# Power.net
KiCad netlist of a schematic drawn in Altium Designer
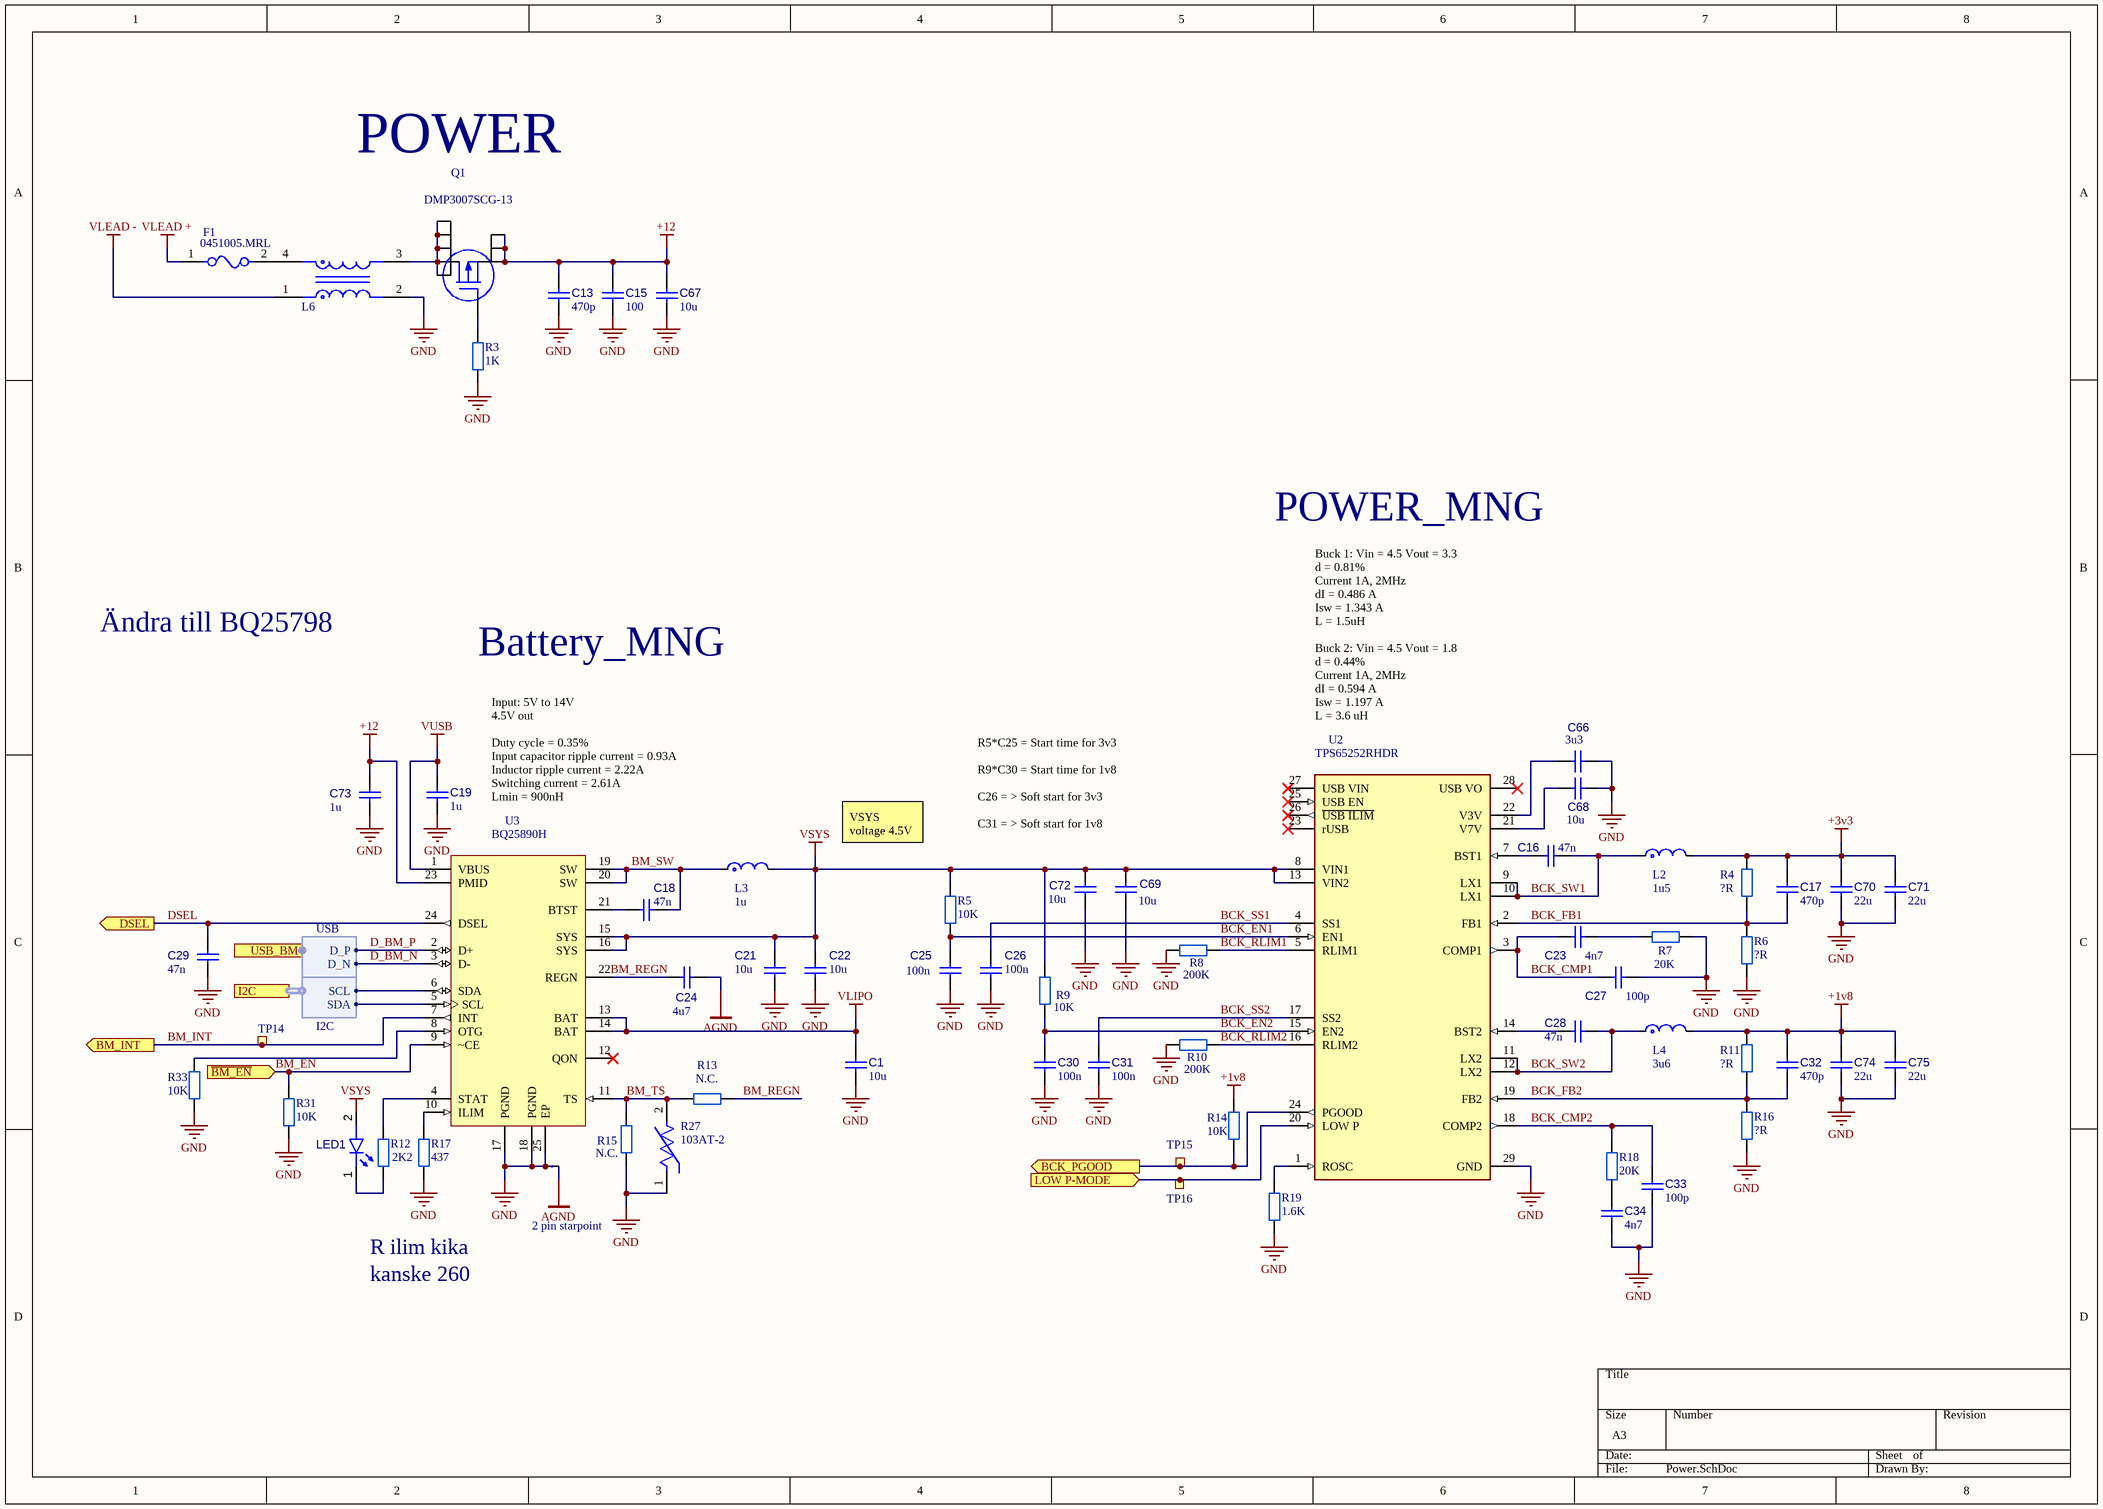
[diagram p0: Power.SchDoc]

(export (version "E")
  (design (tool "Eeschema 10.0.6"))
  (components
    (comp (ref "C1")
      (value "10u")
      (footprint "CAPC1608X90X40LL10T20 HD")
      (description "Chip Capacitor, 0603 (1608 Metric)")
      (fields (field (name "TOLERANCE") "?%") (field (name "Comment") "Capacitor 0603"))
      (libsource (lib "Motonaut") (part "CAP-NP-2"))
    )
    (comp (ref "C13")
      (value "470p")
      (footprint "CAPC2013X95X50LL10T25 HD")
      (description "Chip Capacitor, 0805 (2012 Metric)")
      (fields (field (name "TOLERANCE") "?%") (field (name "Comment") "Capacitor 0805"))
      (libsource (lib "Motonaut") (part "CAP-NP-2"))
    )
    (comp (ref "C15")
      (value "100")
      (footprint "CAPC1608X90X40LL10T20 HD")
      (description "Chip Capacitor, 0603 (1608 Metric)")
      (fields (field (name "TOLERANCE") "?%") (field (name "Comment") "Capacitor 0603"))
      (libsource (lib "Motonaut") (part "CAP-NP-2"))
    )
    (comp (ref "C16")
      (value "47n")
      (footprint "CAPC1005X55X25LL05T10 HD")
      (description "Chip Capacitor, 0402 (1005 Metric)")
      (fields (field (name "TOLERANCE") "?%") (field (name "Comment") "Capacitor 0402"))
      (libsource (lib "Motonaut") (part "CAP-NP-2"))
    )
    (comp (ref "C17")
      (value "470p")
      (footprint "CAPC1005X55X25LL05T10 HD")
      (description "Chip Capacitor, 0402 (1005 Metric)")
      (fields (field (name "TOLERANCE") "?%") (field (name "Comment") "Capacitor 0402"))
      (libsource (lib "Motonaut") (part "CAP-NP-2"))
    )
    (comp (ref "C18")
      (value "47n")
      (footprint "CAPC1005X55X25LL05T10 HD")
      (description "Chip Capacitor, 0402 (1005 Metric)")
      (fields (field (name "TOLERANCE") "?%") (field (name "Comment") "Capacitor 0402"))
      (libsource (lib "Motonaut") (part "CAP-NP-2"))
    )
    (comp (ref "C19")
      (value "1u")
      (footprint "CAPC1005X55X25LL05T10 HD")
      (description "Chip Capacitor, 0402 (1005 Metric)")
      (fields (field (name "TOLERANCE") "?%") (field (name "Comment") "Capacitor 0402"))
      (libsource (lib "Motonaut") (part "CAP-NP-2"))
    )
    (comp (ref "C21")
      (value "10u")
      (footprint "CAPC1608X90X40LL10T20 HD")
      (description "Chip Capacitor, 0603 (1608 Metric)")
      (fields (field (name "TOLERANCE") "?%") (field (name "Comment") "Capacitor 0603"))
      (libsource (lib "Motonaut") (part "CAP-NP-2"))
    )
    (comp (ref "C22")
      (value "10u")
      (footprint "CAPC1608X90X40LL10T20 HD")
      (description "Chip Capacitor, 0603 (1608 Metric)")
      (fields (field (name "TOLERANCE") "?%") (field (name "Comment") "Capacitor 0603"))
      (libsource (lib "Motonaut") (part "CAP-NP-2"))
    )
    (comp (ref "C23")
      (value "4n7")
      (footprint "CAPC1005X55X25LL05T10 HD")
      (description "Chip Capacitor, 0402 (1005 Metric)")
      (fields (field (name "TOLERANCE") "?%") (field (name "Comment") "Capacitor 0402"))
      (libsource (lib "Motonaut") (part "CAP-NP-2"))
    )
    (comp (ref "C24")
      (value "4u7")
      (footprint "CAPC1608X90X40LL10T20 HD")
      (description "Chip Capacitor, 0603 (1608 Metric)")
      (fields (field (name "TOLERANCE") "?%") (field (name "Comment") "Capacitor 0603"))
      (libsource (lib "Motonaut") (part "CAP-NP-2"))
    )
    (comp (ref "C25")
      (value "100n")
      (footprint "CAPC1005X55X25LL05T10 HD")
      (description "Chip Capacitor, 0402 (1005 Metric)")
      (fields (field (name "TOLERANCE") "?%") (field (name "Comment") "Capacitor 0402"))
      (libsource (lib "Motonaut") (part "CAP-NP-2"))
    )
    (comp (ref "C26")
      (value "100n")
      (footprint "CAPC1005X55X25LL05T10 HD")
      (description "Chip Capacitor, 0402 (1005 Metric)")
      (fields (field (name "TOLERANCE") "?%") (field (name "Comment") "Capacitor 0402"))
      (libsource (lib "Motonaut") (part "CAP-NP-2"))
    )
    (comp (ref "C27")
      (value "100p")
      (footprint "CAPC1005X55X25LL05T10 HD")
      (description "Chip Capacitor, 0402 (1005 Metric)")
      (fields (field (name "TOLERANCE") "?%") (field (name "Comment") "Capacitor 0402"))
      (libsource (lib "Motonaut") (part "CAP-NP-2"))
    )
    (comp (ref "C28")
      (value "47n")
      (footprint "CAPC1005X55X25LL05T10 HD")
      (description "Chip Capacitor, 0402 (1005 Metric)")
      (fields (field (name "TOLERANCE") "?%") (field (name "Comment") "Capacitor 0402"))
      (libsource (lib "Motonaut") (part "CAP-NP-2"))
    )
    (comp (ref "C29")
      (value "47n")
      (footprint "CAPC1005X55X25LL05T10 HD")
      (description "Chip Capacitor, 0402 (1005 Metric)")
      (fields (field (name "TOLERANCE") "?%") (field (name "Comment") "Capacitor 0402"))
      (libsource (lib "Motonaut") (part "CAP-NP-2"))
    )
    (comp (ref "C30")
      (value "100n")
      (footprint "CAPC1005X55X25LL05T10 HD")
      (description "Chip Capacitor, 0402 (1005 Metric)")
      (fields (field (name "TOLERANCE") "?%") (field (name "Comment") "Capacitor 0402"))
      (libsource (lib "Motonaut") (part "CAP-NP-2"))
    )
    (comp (ref "C31")
      (value "100n")
      (footprint "CAPC1005X55X25LL05T10 HD")
      (description "Chip Capacitor, 0402 (1005 Metric)")
      (fields (field (name "TOLERANCE") "?%") (field (name "Comment") "Capacitor 0402"))
      (libsource (lib "Motonaut") (part "CAP-NP-2"))
    )
    (comp (ref "C32")
      (value "470p")
      (footprint "CAPC1005X55X25LL05T10 HD")
      (description "Chip Capacitor, 0402 (1005 Metric)")
      (fields (field (name "TOLERANCE") "?%") (field (name "Comment") "Capacitor 0402"))
      (libsource (lib "Motonaut") (part "CAP-NP-2"))
    )
    (comp (ref "C33")
      (value "100p")
      (footprint "CAPC1005X55X25LL05T10 HD")
      (description "Chip Capacitor, 0402 (1005 Metric)")
      (fields (field (name "TOLERANCE") "?%") (field (name "Comment") "Capacitor 0402"))
      (libsource (lib "Motonaut") (part "CAP-NP-2"))
    )
    (comp (ref "C34")
      (value "4n7")
      (footprint "CAPC1005X55X25LL05T10 HD")
      (description "Chip Capacitor, 0402 (1005 Metric)")
      (fields (field (name "TOLERANCE") "?%") (field (name "Comment") "Capacitor 0402"))
      (libsource (lib "Motonaut") (part "CAP-NP-2"))
    )
    (comp (ref "C66")
      (value "3u3")
      (footprint "CAPC1608X90X40LL10T20 HD")
      (description "Chip Capacitor, 0603 (1608 Metric)")
      (fields (field (name "TOLERANCE") "?%") (field (name "Comment") "Capacitor 0603"))
      (libsource (lib "Motonaut") (part "CAP-NP-2"))
    )
    (comp (ref "C67")
      (value "10u")
      (footprint "CAPC1608X90X40LL10T20 HD")
      (description "Chip Capacitor, 0603 (1608 Metric)")
      (fields (field (name "TOLERANCE") "?%") (field (name "Comment") "Capacitor 0603"))
      (libsource (lib "Motonaut") (part "CAP-NP-2"))
    )
    (comp (ref "C68")
      (value "10u")
      (footprint "CAPC1608X90X40LL10T20 HD")
      (description "Chip Capacitor, 0603 (1608 Metric)")
      (fields (field (name "TOLERANCE") "?%") (field (name "Comment") "Capacitor 0603"))
      (libsource (lib "Motonaut") (part "CAP-NP-2"))
    )
    (comp (ref "C69")
      (value "10u")
      (footprint "CAPC1608X90X40LL10T20 HD")
      (description "Chip Capacitor, 0603 (1608 Metric)")
      (fields (field (name "TOLERANCE") "?%") (field (name "Comment") "Capacitor 0603"))
      (libsource (lib "Motonaut") (part "CAP-NP-2"))
    )
    (comp (ref "C70")
      (value "22u")
      (footprint "CAPC1608X90X40LL10T20 HD")
      (description "Chip Capacitor, 0603 (1608 Metric)")
      (fields (field (name "TOLERANCE") "?%") (field (name "Comment") "Capacitor 0603"))
      (libsource (lib "Motonaut") (part "CAP-NP-2"))
    )
    (comp (ref "C71")
      (value "22u")
      (footprint "CAPC1608X90X40LL10T20 HD")
      (description "Chip Capacitor, 0603 (1608 Metric)")
      (fields (field (name "TOLERANCE") "?%") (field (name "Comment") "Capacitor 0603"))
      (libsource (lib "Motonaut") (part "CAP-NP-2"))
    )
    (comp (ref "C72")
      (value "10u")
      (footprint "CAPC1608X90X40LL10T20 HD")
      (description "Chip Capacitor, 0603 (1608 Metric)")
      (fields (field (name "TOLERANCE") "?%") (field (name "Comment") "Capacitor 0603"))
      (libsource (lib "Motonaut") (part "CAP-NP-2"))
    )
    (comp (ref "C73")
      (value "1u")
      (footprint "CAPC1005X55X25LL05T10 HD")
      (description "Chip Capacitor, 0402 (1005 Metric)")
      (fields (field (name "TOLERANCE") "?%") (field (name "Comment") "Capacitor 0402"))
      (libsource (lib "Motonaut") (part "CAP-NP-2"))
    )
    (comp (ref "C74")
      (value "22u")
      (footprint "CAPC1608X90X40LL10T20 HD")
      (description "Chip Capacitor, 0603 (1608 Metric)")
      (fields (field (name "TOLERANCE") "?%") (field (name "Comment") "Capacitor 0603"))
      (libsource (lib "Motonaut") (part "CAP-NP-2"))
    )
    (comp (ref "C75")
      (value "22u")
      (footprint "CAPC1608X90X40LL10T20 HD")
      (description "Chip Capacitor, 0603 (1608 Metric)")
      (fields (field (name "TOLERANCE") "?%") (field (name "Comment") "Capacitor 0603"))
      (libsource (lib "Motonaut") (part "CAP-NP-2"))
    )
    (comp (ref "F1")
      (value "0451005.MRL")
      (footprint "FP-0451-MFG")
      (description "FUSE BRD MNT 5A 125VAC/VDC 2SMD")
      (fields
        (field (name "OCTOPART") "https://octopart.com/0451005.mrl-littelfuse-566389")
        (field (name "MANUFACTURER") "Littelfuse Inc")
      )
      (libsource (lib "Altium Content Vault") (part "5bcf9b9f640e542cf0359d10258e979"))
    )
    (comp (ref "L2")
      (value "1u5")
      (footprint "INDC2013X105X50NL20T20")
      (description "Inductor RF Chip Thin Film 0805")
      (fields (field (name "Comment") "Inductor 0805"))
      (libsource (lib "Motonaut") (part "4cc4b267dca4c8e51f7102f422741d8"))
    )
    (comp (ref "L3")
      (value "Inductor 0805")
      (footprint "INDC2013X105X50NL20T20")
      (description "Inductor RF Chip Thin Film 0805")
      (fields (field (name "INDUCTANCE") "1u"))
      (libsource (lib "Motonaut") (part "4cc4b267dca4c8e51f7102f422741d8"))
    )
    (comp (ref "L4")
      (value "3u6")
      (footprint "INDC2013X105X50NL20T20")
      (description "Inductor RF Chip Thin Film 0805")
      (fields (field (name "Comment") "Inductor 0805"))
      (libsource (lib "Motonaut") (part "4cc4b267dca4c8e51f7102f422741d8"))
    )
    (comp (ref "L6")
      (value "DLW5ATN231TQ2L")
      (footprint "FP-DLW5A-MFG")
      (description "Ind Common Mode Choke Wirewound 230 Ohm 100MHz 4A Embossed T/R")
      (libsource (lib "Motonaut") (part "7887baa02bf09715630a48d0c47d7b1"))
    )
    (comp (ref "LED1")
      (value "QBLP595-R")
      (footprint "QTB-QBLP595_V")
      (description "Chip LED 0402, Red, 0.02 A, 2.0 to 2.5 V, -40 to 80 degC, 2-Pin SMD, RoHS, Tape and Reel")
      (libsource (lib "Motonaut") (part "LED-KA-2"))
    )
    (comp (ref "Q1")
      (value "DMP3007SCG-13")
      (footprint "DMP3007SCG13")
      (description "Trans MOSFET P-CH 30V 50A 8-Pin VDFN EP T/R")
      (fields (field (name "MOUSER PART NUMBER") "621-DMP3007SCG-13"))
      (libsource (lib "Motonaut") (part "TRANS-MOSFET-3"))
    )
    (comp (ref "R3")
      (value "1K")
      (footprint "RESC1005X40X25LL10T10 HD")
      (description "Resistor 0403")
      (libsource (lib "Motonaut") (part "Resistor EU"))
    )
    (comp (ref "R4")
      (value "?R")
      (footprint "RESC1005X40X25LL10T10 HD")
      (description "Resistor 0403")
      (libsource (lib "Motonaut") (part "Resistor EU"))
    )
    (comp (ref "R5")
      (value "10K")
      (footprint "RESC1005X40X25LL10T10 HD")
      (description "Resistor 0403")
      (libsource (lib "Motonaut") (part "Resistor EU"))
    )
    (comp (ref "R6")
      (value "?R")
      (footprint "RESC1005X40X25LL10T10 HD")
      (description "Resistor 0403")
      (libsource (lib "Motonaut") (part "Resistor EU"))
    )
    (comp (ref "R7")
      (value "20K")
      (footprint "RESC1005X40X25LL10T10 HD")
      (description "Resistor 0403")
      (libsource (lib "Motonaut") (part "Resistor EU"))
    )
    (comp (ref "R8")
      (value "200K")
      (footprint "RESC1005X40X25LL10T10 HD")
      (description "Resistor 0403")
      (libsource (lib "Motonaut") (part "Resistor EU"))
    )
    (comp (ref "R9")
      (value "10K")
      (footprint "RESC1005X40X25LL10T10 HD")
      (description "Resistor 0403")
      (libsource (lib "Motonaut") (part "Resistor EU"))
    )
    (comp (ref "R10")
      (value "200K")
      (footprint "RESC1005X40X25LL10T10 HD")
      (description "Resistor 0403")
      (libsource (lib "Motonaut") (part "Resistor EU"))
    )
    (comp (ref "R11")
      (value "?R")
      (footprint "RESC1005X40X25LL10T10 HD")
      (description "Resistor 0403")
      (libsource (lib "Motonaut") (part "Resistor EU"))
    )
    (comp (ref "R12")
      (value "2K2")
      (footprint "RESC1005X40X25LL10T10 HD")
      (description "Resistor 0403")
      (libsource (lib "Motonaut") (part "Resistor EU"))
    )
    (comp (ref "R13")
      (value "N.C.")
      (footprint "RESC1005X40X25LL10T10 HD")
      (description "Resistor 0403")
      (libsource (lib "Motonaut") (part "Resistor EU"))
    )
    (comp (ref "R14")
      (value "10K")
      (footprint "RESC1005X40X25LL10T10 HD")
      (description "Resistor 0403")
      (libsource (lib "Motonaut") (part "Resistor EU"))
    )
    (comp (ref "R15")
      (value "N.C.")
      (footprint "RESC1005X40X25LL10T10 HD")
      (description "Resistor 0403")
      (libsource (lib "Motonaut") (part "Resistor EU"))
    )
    (comp (ref "R16")
      (value "?R")
      (footprint "RESC1005X40X25LL10T10 HD")
      (description "Resistor 0403")
      (libsource (lib "Motonaut") (part "Resistor EU"))
    )
    (comp (ref "R17")
      (value "437")
      (footprint "RESC1005X40X25LL10T10 HD")
      (description "Resistor 0403")
      (libsource (lib "Motonaut") (part "Resistor EU"))
    )
    (comp (ref "R18")
      (value "20K")
      (footprint "RESC1005X40X25LL10T10 HD")
      (description "Resistor 0403")
      (libsource (lib "Motonaut") (part "Resistor EU"))
    )
    (comp (ref "R19")
      (value "1.6K")
      (footprint "RESC1005X40X25LL10T10 HD")
      (description "Resistor 0403")
      (libsource (lib "Motonaut") (part "Resistor EU"))
    )
    (comp (ref "R27")
      (value "103AT-2")
      (footprint "FP-103AT-2-MFG")
      (description "Thermistor NTC 10KOhm 1% 2-Pin")
      (fields (field (name "TOLERANCE") "1%"))
      (libsource (lib "Altium Content Vault") (part "3b148a6ebabc5fb4d708a66c052d352"))
    )
    (comp (ref "R31")
      (value "10K")
      (footprint "RESC1005X40X25LL10T10 HD")
      (description "Resistor 0403")
      (libsource (lib "Motonaut") (part "Resistor EU"))
    )
    (comp (ref "R33")
      (value "10K")
      (footprint "RESC1005X40X25LL10T10 HD")
      (description "Resistor 0403")
      (libsource (lib "Motonaut") (part "Resistor EU"))
    )
    (comp (ref "ST1")
      (value "2 pin starpoint")
      (footprint "2 PIN STARPOINT")
      (description "Starpoint")
      (fields (field (name "MANUFACTURER PART NUMBER") "N.A."))
      (libsource (lib "Motonaut") (part "2 pin starpoint"))
    )
    (comp (ref "TP14")
      (value "TP_SMD_Ø0.7MM")
      (footprint "TP_SMD_Ø0.7mm")
      (description "0.7mm circular SMD testpad")
      (fields
        (field (name "MANUFACTURER") "Nordic Semiconductor")
        (field (name "MANUFACTURER PART NUMBER") "N.A.")
      )
      (libsource (lib "") (part "TP_SMD_Ø1.5MM_1"))
    )
    (comp (ref "TP15")
      (value "TP_SMD_Ø0.7MM")
      (footprint "TP_SMD_Ø0.7mm")
      (description "0.7mm circular SMD testpad")
      (fields
        (field (name "MANUFACTURER") "Nordic Semiconductor")
        (field (name "MANUFACTURER PART NUMBER") "N.A.")
      )
      (libsource (lib "") (part "TP_SMD_Ø1.5MM_1"))
    )
    (comp (ref "TP16")
      (value "TP_SMD_Ø0.7MM")
      (footprint "TP_SMD_Ø0.7mm")
      (description "0.7mm circular SMD testpad")
      (fields
        (field (name "MANUFACTURER") "Nordic Semiconductor")
        (field (name "MANUFACTURER PART NUMBER") "N.A.")
      )
      (libsource (lib "Motonaut") (part "TP_SMD_Ø1.5MM"))
    )
    (comp (ref "U2")
      (value "TPS65252RHDR")
      (footprint "FP-RHD0028A-MFG")
      (description "TPS65252 4.5V to 16V Input, 3A/2")
      (libsource (lib "Motonaut") (part "3429b10e55eaba375a40ad71d7ce87b"))
    )
    (comp (ref "U3")
      (value "BQ25890H")
      (footprint "QFN50P400X400X80-25N-D")
      (libsource (lib "Motonaut") (part "BQ25890H"))
    )
  )
  (nets
    (net (code "3") (name "+1v8") (class "Default")
      (node (ref "C32") (pin "2") (pinfunction "2_2") (pintype "passive"))
      (node (ref "C74") (pin "2") (pinfunction "2_2") (pintype "passive"))
      (node (ref "C75") (pin "2") (pinfunction "2_2") (pintype "passive"))
      (node (ref "L4") (pin "2") (pinfunction "2_2") (pintype "passive"))
      (node (ref "R11") (pin "2") (pinfunction "2_2") (pintype "passive"))
      (node (ref "R14") (pin "2") (pinfunction "2_2") (pintype "passive"))
    )
    (net (code "4") (name "+3v3") (class "Default")
      (node (ref "C17") (pin "2") (pinfunction "2_2") (pintype "passive"))
      (node (ref "C70") (pin "2") (pinfunction "2_2") (pintype "passive"))
      (node (ref "C71") (pin "2") (pinfunction "2_2") (pintype "passive"))
      (node (ref "L2") (pin "2") (pinfunction "2_2") (pintype "passive"))
      (node (ref "R4") (pin "2") (pinfunction "2_2") (pintype "passive"))
    )
    (net (code "5") (name "+12") (class "Default")
      (node (ref "C13") (pin "2") (pinfunction "2_2") (pintype "passive"))
      (node (ref "C15") (pin "2") (pinfunction "2_2") (pintype "passive"))
      (node (ref "C67") (pin "2") (pinfunction "2_2") (pintype "passive"))
      (node (ref "C73") (pin "2") (pinfunction "2_2") (pintype "passive"))
      (node (ref "Q1") (pin "1") (pinfunction "S_1") (pintype "passive"))
      (node (ref "Q1") (pin "2") (pinfunction "S_2") (pintype "passive"))
      (node (ref "Q1") (pin "3") (pinfunction "S_3") (pintype "passive"))
      (node (ref "U3") (pin "23") (pinfunction "PMID_23") (pintype "power_in"))
    )
    (net (code "6") (name "/BCK_CMP1") (class "Default")
      (node (ref "C23") (pin "1") (pinfunction "1_1") (pintype "passive"))
      (node (ref "C27") (pin "2") (pinfunction "2_2") (pintype "passive"))
      (node (ref "U2") (pin "3") (pinfunction "COMP1_3") (pintype "output"))
    )
    (net (code "7") (name "/BCK_CMP2") (class "Default")
      (node (ref "C33") (pin "2") (pinfunction "2_2") (pintype "passive"))
      (node (ref "R18") (pin "2") (pinfunction "2_2") (pintype "passive"))
      (node (ref "U2") (pin "18") (pinfunction "COMP2_18") (pintype "output"))
    )
    (net (code "8") (name "/BCK_EN1") (class "Default")
      (node (ref "C25") (pin "2") (pinfunction "2_2") (pintype "passive"))
      (node (ref "R5") (pin "1") (pinfunction "1_1") (pintype "passive"))
      (node (ref "U2") (pin "6") (pinfunction "EN1_6") (pintype "input"))
    )
    (net (code "9") (name "/BCK_EN2") (class "Default")
      (node (ref "C30") (pin "2") (pinfunction "2_2") (pintype "passive"))
      (node (ref "R9") (pin "1") (pinfunction "1_1") (pintype "passive"))
      (node (ref "U2") (pin "15") (pinfunction "EN2_15") (pintype "input"))
    )
    (net (code "10") (name "/BCK_FB1") (class "Default")
      (node (ref "C17") (pin "1") (pinfunction "1_1") (pintype "passive"))
      (node (ref "R4") (pin "1") (pinfunction "1_1") (pintype "passive"))
      (node (ref "R6") (pin "2") (pinfunction "2_2") (pintype "passive"))
      (node (ref "U2") (pin "2") (pinfunction "FB1_2") (pintype "input"))
    )
    (net (code "11") (name "/BCK_FB2") (class "Default")
      (node (ref "C32") (pin "1") (pinfunction "1_1") (pintype "passive"))
      (node (ref "R11") (pin "1") (pinfunction "1_1") (pintype "passive"))
      (node (ref "R16") (pin "2") (pinfunction "2_2") (pintype "passive"))
      (node (ref "U2") (pin "19") (pinfunction "FB2_19") (pintype "input"))
    )
    (net (code "12") (name "/BCK_PGOOD") (class "Default")
      (node (ref "R14") (pin "1") (pinfunction "1_1") (pintype "passive"))
      (node (ref "TP15") (pin "1") (pinfunction "1_1") (pintype "passive"))
      (node (ref "U2") (pin "24") (pinfunction "PGOOD_24") (pintype "output"))
    )
    (net (code "13") (name "/BCK_RLIM1") (class "Default")
      (node (ref "R8") (pin "2") (pinfunction "2_2") (pintype "passive"))
      (node (ref "U2") (pin "5") (pinfunction "RLIM1_5") (pintype "passive"))
    )
    (net (code "14") (name "/BCK_RLIM2") (class "Default")
      (node (ref "R10") (pin "2") (pinfunction "2_2") (pintype "passive"))
      (node (ref "U2") (pin "16") (pinfunction "RLIM2_16") (pintype "passive"))
    )
    (net (code "15") (name "/BCK_SS1") (class "Default")
      (node (ref "C26") (pin "2") (pinfunction "2_2") (pintype "passive"))
      (node (ref "U2") (pin "4") (pinfunction "SS1_4") (pintype "passive"))
    )
    (net (code "16") (name "/BCK_SS2") (class "Default")
      (node (ref "C31") (pin "2") (pinfunction "2_2") (pintype "passive"))
      (node (ref "U2") (pin "17") (pinfunction "SS2_17") (pintype "passive"))
    )
    (net (code "17") (name "/BCK_SW1") (class "Default")
      (node (ref "C16") (pin "2") (pinfunction "2_2") (pintype "passive"))
      (node (ref "L2") (pin "1") (pinfunction "1_1") (pintype "passive"))
      (node (ref "U2") (pin "10") (pinfunction "LX1_10") (pintype "power_in"))
      (node (ref "U2") (pin "9") (pinfunction "LX1_9") (pintype "power_in"))
    )
    (net (code "18") (name "/BCK_SW2") (class "Default")
      (node (ref "C28") (pin "2") (pinfunction "2_2") (pintype "passive"))
      (node (ref "L4") (pin "1") (pinfunction "1_1") (pintype "passive"))
      (node (ref "U2") (pin "11") (pinfunction "LX2_11") (pintype "power_in"))
      (node (ref "U2") (pin "12") (pinfunction "LX2_12") (pintype "power_in"))
    )
    (net (code "19") (name "/BM_INT") (class "Default")
      (node (ref "TP14") (pin "1") (pinfunction "1_1") (pintype "passive"))
      (node (ref "U3") (pin "7") (pinfunction "INT_7") (pintype "output"))
    )
    (net (code "20") (name "/BM_REGN") (class "Default")
      (node (ref "C24") (pin "1") (pinfunction "1_1") (pintype "passive"))
      (node (ref "R13") (pin "2") (pinfunction "2_2") (pintype "passive"))
      (node (ref "U3") (pin "22") (pinfunction "REGN_22") (pintype "passive"))
    )
    (net (code "21") (name "/BM_SW") (class "Default")
      (node (ref "C18") (pin "2") (pinfunction "2_2") (pintype "passive"))
      (node (ref "L3") (pin "1") (pinfunction "1_1") (pintype "passive"))
      (node (ref "U3") (pin "19") (pinfunction "SW_19") (pintype "power_in"))
      (node (ref "U3") (pin "20") (pinfunction "SW_20") (pintype "power_in"))
    )
    (net (code "22") (name "/BM_TS") (class "Default")
      (node (ref "R13") (pin "1") (pinfunction "1_1") (pintype "passive"))
      (node (ref "R15") (pin "2") (pinfunction "2_2") (pintype "passive"))
      (node (ref "R27") (pin "2") (pinfunction "2_2") (pintype "passive"))
      (node (ref "U3") (pin "11") (pinfunction "TS_11") (pintype "input"))
    )
    (net (code "23") (name "/BM_~{EN}") (class "Default")
      (node (ref "R31") (pin "2") (pinfunction "2_2") (pintype "passive"))
      (node (ref "U3") (pin "9") (pinfunction "~CE_9") (pintype "input"))
    )
    (net (code "24") (name "/DSEL") (class "Default")
      (node (ref "C29") (pin "2") (pinfunction "2_2") (pintype "passive"))
      (node (ref "U3") (pin "24") (pinfunction "DSEL_24") (pintype "output"))
    )
    (net (code "25") (name "/D_BM_N") (class "Default")
      (node (ref "U3") (pin "3") (pinfunction "D-_3") (pintype "bidirectional"))
    )
    (net (code "26") (name "/D_BM_P") (class "Default")
      (node (ref "U3") (pin "2") (pinfunction "D+_2") (pintype "bidirectional"))
    )
    (net (code "27") (name "/LOW P-MODE") (class "Default")
      (node (ref "TP16") (pin "1") (pinfunction "1_1") (pintype "passive"))
      (node (ref "U2") (pin "20") (pinfunction "LOW_P_20") (pintype "input"))
    )
    (net (code "28") (name "/SCL") (class "Default")
      (node (ref "U3") (pin "6") (pinfunction "SDA_6") (pintype "bidirectional"))
    )
    (net (code "29") (name "/SDA") (class "Default")
      (node (ref "U3") (pin "5") (pinfunction "SCL_5") (pintype "input"))
    )
    (net (code "32") (name "AGND") (class "Default")
      (node (ref "C24") (pin "2") (pinfunction "2_2") (pintype "passive"))
      (node (ref "ST1") (pin "2") (pintype "passive"))
    )
    (net (code "33") (name "GND") (class "Default")
      (node (ref "C1") (pin "1") (pinfunction "1_1") (pintype "passive"))
      (node (ref "C13") (pin "1") (pinfunction "1_1") (pintype "passive"))
      (node (ref "C15") (pin "1") (pinfunction "1_1") (pintype "passive"))
      (node (ref "C19") (pin "1") (pinfunction "1_1") (pintype "passive"))
      (node (ref "C21") (pin "1") (pinfunction "1_1") (pintype "passive"))
      (node (ref "C22") (pin "1") (pinfunction "1_1") (pintype "passive"))
      (node (ref "C25") (pin "1") (pinfunction "1_1") (pintype "passive"))
      (node (ref "C26") (pin "1") (pinfunction "1_1") (pintype "passive"))
      (node (ref "C27") (pin "1") (pinfunction "1_1") (pintype "passive"))
      (node (ref "C29") (pin "1") (pinfunction "1_1") (pintype "passive"))
      (node (ref "C30") (pin "1") (pinfunction "1_1") (pintype "passive"))
      (node (ref "C31") (pin "1") (pinfunction "1_1") (pintype "passive"))
      (node (ref "C33") (pin "1") (pinfunction "1_1") (pintype "passive"))
      (node (ref "C34") (pin "1") (pinfunction "1_1") (pintype "passive"))
      (node (ref "C66") (pin "1") (pinfunction "1_1") (pintype "passive"))
      (node (ref "C67") (pin "1") (pinfunction "1_1") (pintype "passive"))
      (node (ref "C68") (pin "1") (pinfunction "1_1") (pintype "passive"))
      (node (ref "C69") (pin "1") (pinfunction "1_1") (pintype "passive"))
      (node (ref "C70") (pin "1") (pinfunction "1_1") (pintype "passive"))
      (node (ref "C71") (pin "1") (pinfunction "1_1") (pintype "passive"))
      (node (ref "C72") (pin "1") (pinfunction "1_1") (pintype "passive"))
      (node (ref "C73") (pin "1") (pinfunction "1_1") (pintype "passive"))
      (node (ref "C74") (pin "1") (pinfunction "1_1") (pintype "passive"))
      (node (ref "C75") (pin "1") (pinfunction "1_1") (pintype "passive"))
      (node (ref "L6") (pin "2") (pinfunction "2_2") (pintype "passive"))
      (node (ref "R10") (pin "1") (pinfunction "1_1") (pintype "passive"))
      (node (ref "R15") (pin "1") (pinfunction "1_1") (pintype "passive"))
      (node (ref "R16") (pin "1") (pinfunction "1_1") (pintype "passive"))
      (node (ref "R17") (pin "1") (pinfunction "1_1") (pintype "passive"))
      (node (ref "R19") (pin "1") (pinfunction "1_1") (pintype "passive"))
      (node (ref "R27") (pin "1") (pinfunction "1_1") (pintype "passive"))
      (node (ref "R3") (pin "1") (pinfunction "1_1") (pintype "passive"))
      (node (ref "R31") (pin "1") (pinfunction "1_1") (pintype "passive"))
      (node (ref "R33") (pin "1") (pinfunction "1_1") (pintype "passive"))
      (node (ref "R6") (pin "1") (pinfunction "1_1") (pintype "passive"))
      (node (ref "R7") (pin "2") (pinfunction "2_2") (pintype "passive"))
      (node (ref "R8") (pin "1") (pinfunction "1_1") (pintype "passive"))
      (node (ref "ST1") (pin "1") (pintype "passive"))
      (node (ref "U2") (pin "29") (pinfunction "GND_29") (pintype "power_in"))
      (node (ref "U3") (pin "17") (pinfunction "PGND_17") (pintype "passive"))
      (node (ref "U3") (pin "18") (pinfunction "PGND_18") (pintype "passive"))
      (node (ref "U3") (pin "25") (pinfunction "EP_25") (pintype "passive"))
    )
    (net (code "34") (name "Net-(C23-Pad2)") (class "Default")
      (node (ref "C23") (pin "2") (pinfunction "2_2") (pintype "passive"))
      (node (ref "R7") (pin "1") (pinfunction "1_1") (pintype "passive"))
    )
    (net (code "35") (name "Net-(C34-Pad2)") (class "Default")
      (node (ref "C34") (pin "2") (pinfunction "2_2") (pintype "passive"))
      (node (ref "R18") (pin "1") (pinfunction "1_1") (pintype "passive"))
    )
    (net (code "36") (name "Net-(F1-Pad2)") (class "Default")
      (node (ref "F1") (pin "2") (pinfunction "2_2") (pintype "passive"))
      (node (ref "L6") (pin "4") (pinfunction "4_4") (pintype "passive"))
    )
    (net (code "37") (name "Net-(L6-Pad3)") (class "Default")
      (node (ref "L6") (pin "3") (pinfunction "3_3") (pintype "passive"))
      (node (ref "Q1") (pin "5") (pinfunction "D_5") (pintype "passive"))
      (node (ref "Q1") (pin "6") (pinfunction "D_6") (pintype "passive"))
      (node (ref "Q1") (pin "7") (pinfunction "D_7") (pintype "passive"))
      (node (ref "Q1") (pin "8") (pinfunction "D_8") (pintype "passive"))
      (node (ref "Q1") (pin "9") (pinfunction "D_9") (pintype "passive"))
    )
    (net (code "38") (name "Net-(LED1-K)") (class "Default")
      (node (ref "LED1") (pin "1") (pinfunction "K_1") (pintype "passive"))
      (node (ref "R12") (pin "2") (pinfunction "2_2") (pintype "passive"))
    )
    (net (code "39") (name "Net-(Q1-G)") (class "Default")
      (node (ref "Q1") (pin "4") (pinfunction "G_4") (pintype "passive"))
      (node (ref "R3") (pin "2") (pinfunction "2_2") (pintype "passive"))
    )
    (net (code "40") (name "Net-(U2-BST1)") (class "Default")
      (node (ref "C16") (pin "1") (pinfunction "1_1") (pintype "passive"))
      (node (ref "U2") (pin "7") (pinfunction "BST1_7") (pintype "input"))
    )
    (net (code "41") (name "Net-(U2-BST2)") (class "Default")
      (node (ref "C28") (pin "1") (pinfunction "1_1") (pintype "passive"))
      (node (ref "U2") (pin "14") (pinfunction "BST2_14") (pintype "input"))
    )
    (net (code "42") (name "Net-(U2-ROSC)") (class "Default")
      (node (ref "R19") (pin "2") (pinfunction "2_2") (pintype "passive"))
      (node (ref "U2") (pin "1") (pinfunction "ROSC_1") (pintype "input"))
    )
    (net (code "43") (name "Net-(U2-V3V)") (class "Default")
      (node (ref "C66") (pin "2") (pinfunction "2_2") (pintype "passive"))
      (node (ref "U2") (pin "22") (pinfunction "V3V_22") (pintype "power_in"))
    )
    (net (code "44") (name "Net-(U2-V7V)") (class "Default")
      (node (ref "C68") (pin "2") (pinfunction "2_2") (pintype "passive"))
      (node (ref "U2") (pin "21") (pinfunction "V7V_21") (pintype "power_in"))
    )
    (net (code "45") (name "Net-(U3-BTST)") (class "Default")
      (node (ref "C18") (pin "1") (pinfunction "1_1") (pintype "passive"))
      (node (ref "U3") (pin "21") (pinfunction "BTST_21") (pintype "passive"))
    )
    (net (code "46") (name "Net-(U3-ILIM)") (class "Default")
      (node (ref "R17") (pin "2") (pinfunction "2_2") (pintype "passive"))
      (node (ref "U3") (pin "10") (pinfunction "ILIM_10") (pintype "input"))
    )
    (net (code "47") (name "Net-(U3-OTG)") (class "Default")
      (node (ref "R33") (pin "2") (pinfunction "2_2") (pintype "passive"))
      (node (ref "U3") (pin "8") (pinfunction "OTG_8") (pintype "input"))
    )
    (net (code "48") (name "Net-(U3-STAT)") (class "Default")
      (node (ref "R12") (pin "1") (pinfunction "1_1") (pintype "passive"))
      (node (ref "U3") (pin "4") (pinfunction "STAT_4") (pintype "open_collector"))
    )
    (net (code "49") (name "VLEAD +") (class "Default")
      (node (ref "F1") (pin "1") (pinfunction "1_1") (pintype "passive"))
    )
    (net (code "50") (name "VLEAD -") (class "Default")
      (node (ref "L6") (pin "1") (pinfunction "1_1") (pintype "passive"))
    )
    (net (code "51") (name "VLIPO") (class "Default")
      (node (ref "C1") (pin "2") (pinfunction "2_2") (pintype "passive"))
      (node (ref "U3") (pin "13") (pinfunction "BAT_13") (pintype "power_in"))
      (node (ref "U3") (pin "14") (pinfunction "BAT_14") (pintype "power_in"))
    )
    (net (code "52") (name "VSYS") (class "Default")
      (node (ref "C21") (pin "2") (pinfunction "2_2") (pintype "passive"))
      (node (ref "C22") (pin "2") (pinfunction "2_2") (pintype "passive"))
      (node (ref "C69") (pin "2") (pinfunction "2_2") (pintype "passive"))
      (node (ref "C72") (pin "2") (pinfunction "2_2") (pintype "passive"))
      (node (ref "L3") (pin "2") (pinfunction "2_2") (pintype "passive"))
      (node (ref "LED1") (pin "2") (pinfunction "A_2") (pintype "passive"))
      (node (ref "R5") (pin "2") (pinfunction "2_2") (pintype "passive"))
      (node (ref "R9") (pin "2") (pinfunction "2_2") (pintype "passive"))
      (node (ref "U2") (pin "13") (pinfunction "VIN2_13") (pintype "power_in"))
      (node (ref "U2") (pin "8") (pinfunction "VIN1_8") (pintype "power_in"))
      (node (ref "U3") (pin "15") (pinfunction "SYS_15") (pintype "power_in"))
      (node (ref "U3") (pin "16") (pinfunction "SYS_16") (pintype "power_in"))
    )
    (net (code "53") (name "VUSB") (class "Default")
      (node (ref "C19") (pin "2") (pinfunction "2_2") (pintype "passive"))
      (node (ref "U3") (pin "1") (pinfunction "VBUS_1") (pintype "power_in"))
    )
    (net (code "54") (name "unconnected-(U2-USB_EN-Pad25)") (class "Default")
      (node (ref "U2") (pin "25") (pinfunction "USB_EN_25") (pintype "input+no_connect"))
    )
    (net (code "55") (name "unconnected-(U2-USB_VIN-Pad27)") (class "Default")
      (node (ref "U2") (pin "27") (pinfunction "USB_VIN_27") (pintype "power_in+no_connect"))
    )
    (net (code "56") (name "unconnected-(U2-USB_VO-Pad28)") (class "Default")
      (node (ref "U2") (pin "28") (pinfunction "USB_VO_28") (pintype "power_in+no_connect"))
    )
    (net (code "57") (name "unconnected-(U2-rUSB-Pad23)") (class "Default")
      (node (ref "U2") (pin "23") (pinfunction "rUSB_23") (pintype "passive+no_connect"))
    )
    (net (code "58") (name "unconnected-(U2-~{USB_ILIM}-Pad26)") (class "Default")
      (node (ref "U2") (pin "26") (pinfunction "~{USB_ILIM}_26") (pintype "output+no_connect"))
    )
    (net (code "59") (name "unconnected-(U3-QON-Pad12)") (class "Default")
      (node (ref "U3") (pin "12") (pinfunction "QON_12") (pintype "passive+no_connect"))
    )
  )
)
